# heater.net
KiCad netlist of a schematic drawn in Altium Designer
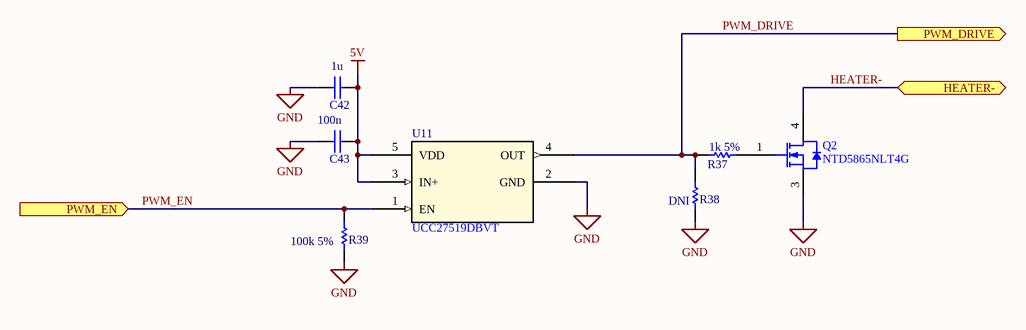
[diagram p0: heater.SchDoc]

(export (version "E")
  (design (tool "Eeschema 10.0.6"))
  (components
    (comp (ref "C42")
      (value "1u")
      (footprint "0805")
      (description "Generic 0805 Capacitor")
      (libsource (lib "symbol_library") (part "C_0805"))
    )
    (comp (ref "C43")
      (value "100n")
      (footprint "0805")
      (description "Generic 0805 Capacitor")
      (libsource (lib "symbol_library") (part "C_0805"))
    )
    (comp (ref "Q2")
      (value "NTD5865NLT4G")
      (footprint "TO-252AA")
      (description "N-Channel 60V 46A (Tc) 71W (Tc) Surface Mount DPAK")
      (libsource (lib "symbol_library") (part "NTD5865NL"))
    )
    (comp (ref "R37")
      (value "1k 5%")
      (footprint "0603")
      (description "Generic 0603 Resistor")
      (libsource (lib "symbol_library") (part "R_0603"))
    )
    (comp (ref "R38")
      (value "DNI")
      (footprint "0603")
      (description "Generic 0603 Resistor")
      (libsource (lib "symbol_library") (part "R_0603"))
    )
    (comp (ref "R39")
      (value "100k 5%")
      (footprint "0603")
      (description "Generic 0603 Resistor")
      (libsource (lib "symbol_library") (part "R_0603"))
    )
    (comp (ref "U11")
      (value "UCC27519DBVT")
      (footprint "DDC0005A_M")
      (description "Low-Side Gate Driver IC Non-Inverting SOT-23-5")
      (libsource (lib "symbol_library") (part "UCC27519"))
    )
  )
  (nets
    (net (code "1") (name "/HEATER-") (class "Default")
      (node (ref "Q2") (pin "4") (pinfunction "D_4") (pintype "passive"))
    )
    (net (code "2") (name "/PWM_DRIVE") (class "Default")
      (node (ref "R37") (pin "1") (pinfunction "1_1") (pintype "passive"))
      (node (ref "R38") (pin "2") (pinfunction "2_2") (pintype "passive"))
      (node (ref "U11") (pin "4") (pinfunction "OUT_4") (pintype "output"))
    )
    (net (code "3") (name "/PWM_EN") (class "Default")
      (node (ref "R39") (pin "2") (pinfunction "2_2") (pintype "passive"))
      (node (ref "U11") (pin "1") (pinfunction "EN_1") (pintype "input"))
    )
    (net (code "4") (name "5V") (class "Default")
      (node (ref "C42") (pin "2") (pinfunction "2_2") (pintype "passive"))
      (node (ref "C43") (pin "2") (pinfunction "2_2") (pintype "passive"))
      (node (ref "U11") (pin "3") (pinfunction "IN+_3") (pintype "input"))
      (node (ref "U11") (pin "5") (pinfunction "VDD_5") (pintype "power_in"))
    )
    (net (code "5") (name "GND") (class "Default")
      (node (ref "C42") (pin "1") (pinfunction "1_1") (pintype "passive"))
      (node (ref "C43") (pin "1") (pinfunction "1_1") (pintype "passive"))
      (node (ref "Q2") (pin "3") (pinfunction "S_3") (pintype "passive"))
      (node (ref "R38") (pin "1") (pinfunction "1_1") (pintype "passive"))
      (node (ref "R39") (pin "1") (pinfunction "1_1") (pintype "passive"))
      (node (ref "U11") (pin "2") (pinfunction "GND_2") (pintype "power_in"))
    )
    (net (code "6") (name "Net-(Q2-G)") (class "Default")
      (node (ref "Q2") (pin "1") (pinfunction "G_1") (pintype "passive"))
      (node (ref "R37") (pin "2") (pinfunction "2_2") (pintype "passive"))
    )
  )
)
